# 7segement4digits1badidea-mk-4-smd.net
KiCad netlist of a schematic drawn in EAGLE
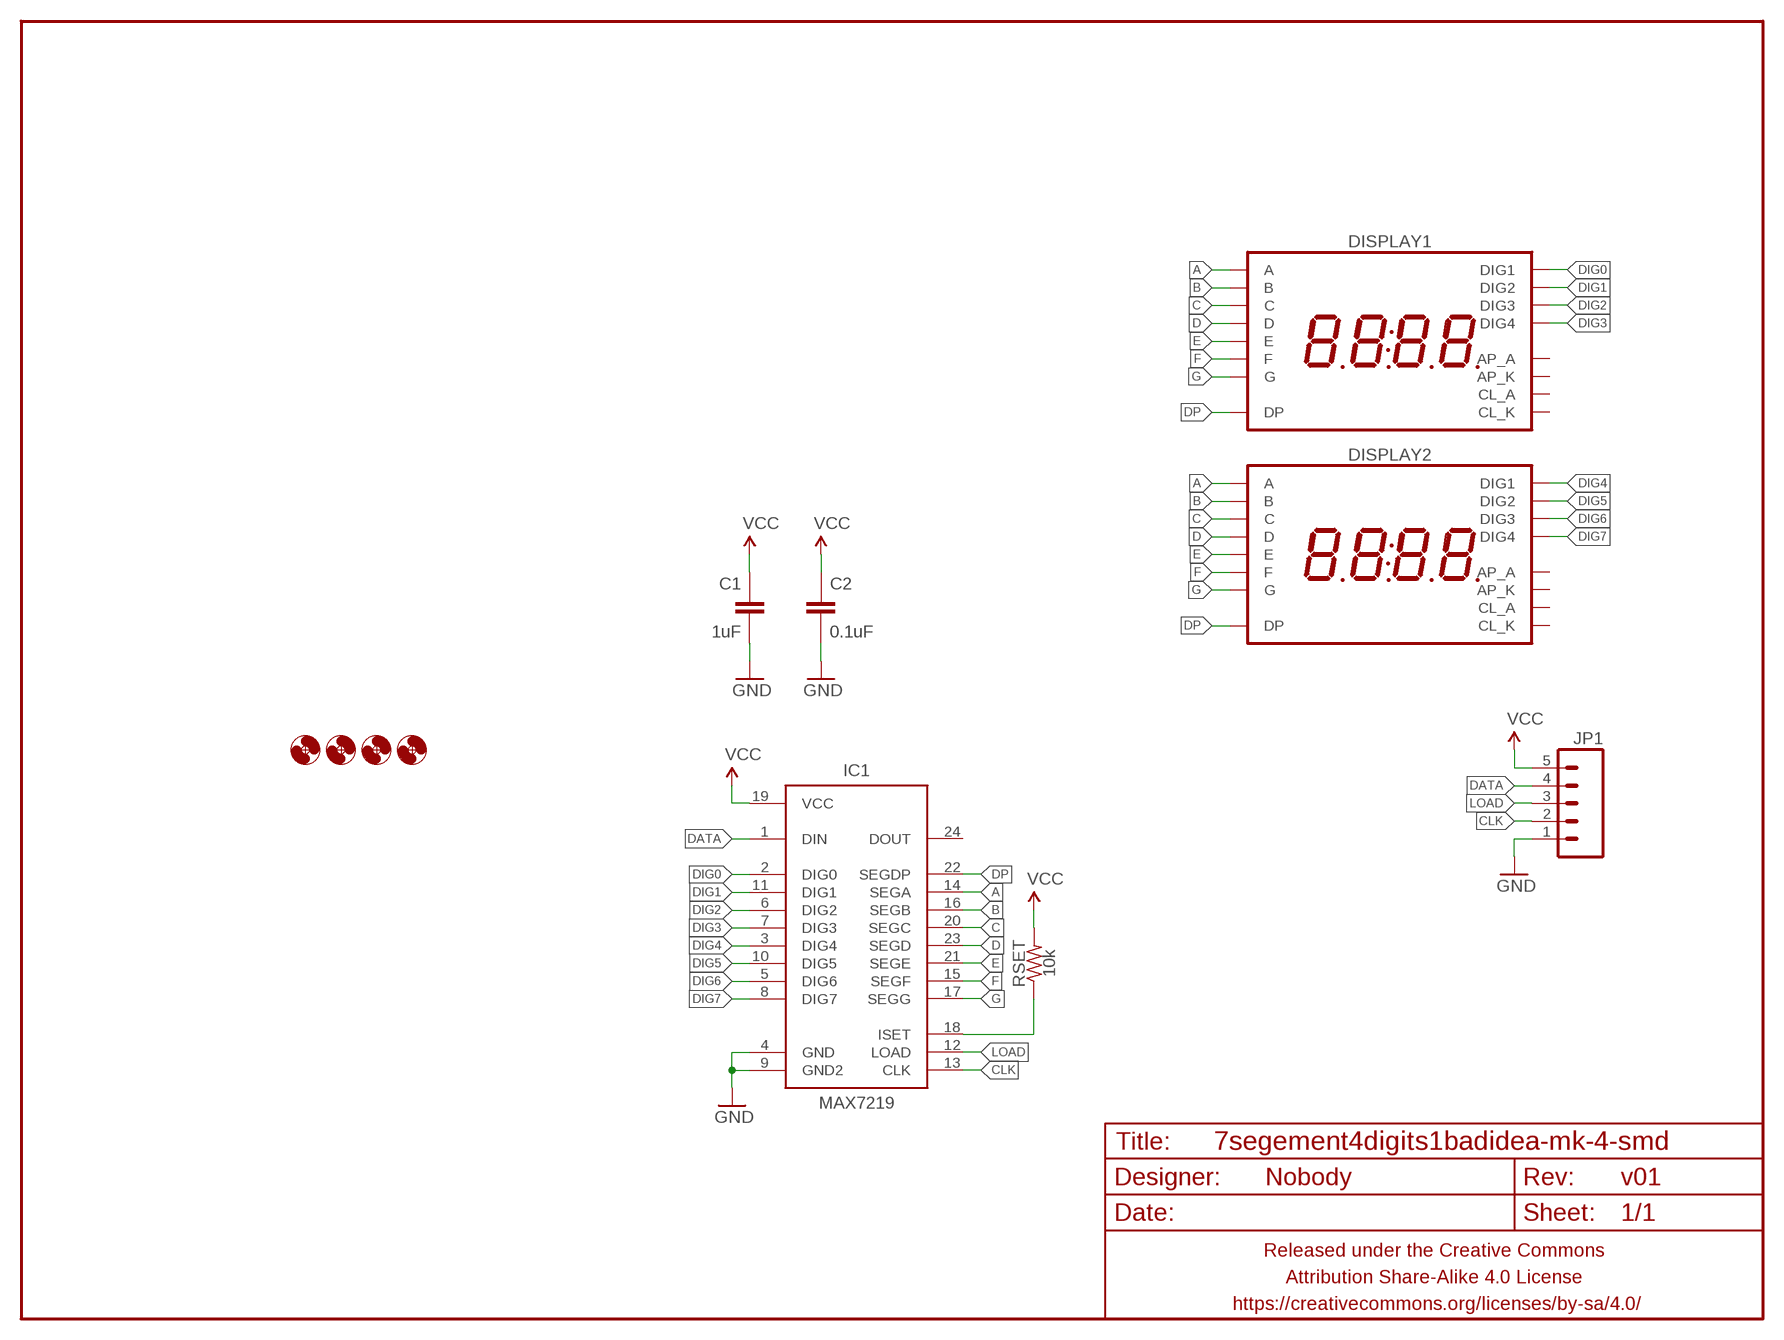
[diagram p0: schematic, sheet 1]

(export (version "E")
  (design (tool "Eeschema 10.0.6"))
  (components
    (comp (ref "C1")
      (value "1uF")
      (footprint "eagle-import:C025-024X044")
      (libsource (lib "eagle-import") (part "CAPACITOR-CERAMIC025-024X044"))
    )
    (comp (ref "C2")
      (value "0.1uF")
      (footprint "eagle-import:C025-024X044")
      (libsource (lib "eagle-import") (part "CAPACITOR-CERAMIC025-024X044"))
    )
    (comp (ref "DISPLAY1")
      (value "7SEG_4DIGIT_COLON_APOS")
      (footprint "eagle-import:7SEG_4DIG_10MM")
      (libsource (lib "eagle-import") (part "7SEG_4DIGIT_COLON_APOS"))
    )
    (comp (ref "DISPLAY2")
      (value "7SEG_4DIGIT_COLON_APOS")
      (footprint "eagle-import:7SEG_4DIG_10MM")
      (libsource (lib "eagle-import") (part "7SEG_4DIGIT_COLON_APOS"))
    )
    (comp (ref "FRAME1")
      (value "FRAME-LETTERNO_PACKAGE")
      (footprint "eagle-import:DUMMY")
      (fields (field (name "DESIGNER") "Nobody"))
      (libsource (lib "eagle-import") (part "FRAME-LETTERNO_PACKAGE"))
    )
    (comp (ref "H1")
      (value "HOLE#2")
      (footprint "eagle-import:HOLE-#2")
      (libsource (lib "eagle-import") (part "HOLE#2"))
    )
    (comp (ref "H2")
      (value "HOLE#2")
      (footprint "eagle-import:HOLE-#2")
      (libsource (lib "eagle-import") (part "HOLE#2"))
    )
    (comp (ref "H3")
      (value "HOLE#2")
      (footprint "eagle-import:HOLE-#2")
      (libsource (lib "eagle-import") (part "HOLE#2"))
    )
    (comp (ref "H4")
      (value "HOLE#2")
      (footprint "eagle-import:HOLE-#2")
      (libsource (lib "eagle-import") (part "HOLE#2"))
    )
    (comp (ref "IC1")
      (value "MAX7219")
      (footprint "eagle-import:SO24W")
      (libsource (lib "eagle-import") (part "MAX7219SOIC-W"))
    )
    (comp (ref "JP1")
      (value "M05PTH")
      (footprint "eagle-import:1X05")
      (libsource (lib "eagle-import") (part "M05PTH"))
    )
    (comp (ref "RSET")
      (value "10k")
      (footprint "eagle-import:RESISTOR-AXIAL-PTH-6.35MM")
      (libsource (lib "eagle-import") (part "RESISTORPTH-AXIAL-6.35MM"))
    )
  )
  (nets
    (net (code "1") (name "A") (class "Default")
      (node (ref "DISPLAY1") (pin "14") (pinfunction "A_14") (pintype "passive"))
      (node (ref "DISPLAY2") (pin "14") (pinfunction "A_14") (pintype "passive"))
      (node (ref "IC1") (pin "14") (pinfunction "SEGA_14") (pintype "bidirectional"))
    )
    (net (code "2") (name "B") (class "Default")
      (node (ref "DISPLAY1") (pin "16") (pinfunction "B_16") (pintype "passive"))
      (node (ref "DISPLAY2") (pin "16") (pinfunction "B_16") (pintype "passive"))
      (node (ref "IC1") (pin "16") (pinfunction "SEGB_16") (pintype "bidirectional"))
    )
    (net (code "3") (name "C") (class "Default")
      (node (ref "DISPLAY1") (pin "13") (pinfunction "C_13") (pintype "passive"))
      (node (ref "DISPLAY2") (pin "13") (pinfunction "C_13") (pintype "passive"))
      (node (ref "IC1") (pin "20") (pinfunction "SEGC_20") (pintype "bidirectional"))
    )
    (net (code "4") (name "CLK") (class "Default")
      (node (ref "IC1") (pin "13") (pinfunction "CLK_13") (pintype "bidirectional"))
      (node (ref "JP1") (pin "2") (pinfunction "2_2") (pintype "passive"))
    )
    (net (code "5") (name "D") (class "Default")
      (node (ref "DISPLAY1") (pin "3") (pinfunction "D_3") (pintype "passive"))
      (node (ref "DISPLAY2") (pin "3") (pinfunction "D_3") (pintype "passive"))
      (node (ref "IC1") (pin "23") (pinfunction "SEGD_23") (pintype "bidirectional"))
    )
    (net (code "6") (name "DATA") (class "Default")
      (node (ref "IC1") (pin "1") (pinfunction "DIN_1") (pintype "bidirectional"))
      (node (ref "JP1") (pin "4") (pinfunction "4_4") (pintype "passive"))
    )
    (net (code "7") (name "DIG0") (class "Default")
      (node (ref "DISPLAY1") (pin "1") (pinfunction "DIG1_1") (pintype "passive"))
      (node (ref "IC1") (pin "2") (pinfunction "DIG0_2") (pintype "bidirectional"))
    )
    (net (code "8") (name "DIG1") (class "Default")
      (node (ref "DISPLAY1") (pin "2") (pinfunction "DIG2_2") (pintype "passive"))
      (node (ref "IC1") (pin "11") (pinfunction "DIG1_11") (pintype "bidirectional"))
    )
    (net (code "9") (name "DIG2") (class "Default")
      (node (ref "DISPLAY1") (pin "6") (pinfunction "DIG3_6") (pintype "passive"))
      (node (ref "IC1") (pin "6") (pinfunction "DIG2_6") (pintype "bidirectional"))
    )
    (net (code "10") (name "DIG3") (class "Default")
      (node (ref "DISPLAY1") (pin "8") (pinfunction "DIG4_8") (pintype "passive"))
      (node (ref "IC1") (pin "7") (pinfunction "DIG3_7") (pintype "bidirectional"))
    )
    (net (code "11") (name "DIG4") (class "Default")
      (node (ref "DISPLAY2") (pin "1") (pinfunction "DIG1_1") (pintype "passive"))
      (node (ref "IC1") (pin "3") (pinfunction "DIG4_3") (pintype "bidirectional"))
    )
    (net (code "12") (name "DIG5") (class "Default")
      (node (ref "DISPLAY2") (pin "2") (pinfunction "DIG2_2") (pintype "passive"))
      (node (ref "IC1") (pin "10") (pinfunction "DIG5_10") (pintype "bidirectional"))
    )
    (net (code "13") (name "DIG6") (class "Default")
      (node (ref "DISPLAY2") (pin "6") (pinfunction "DIG3_6") (pintype "passive"))
      (node (ref "IC1") (pin "5") (pinfunction "DIG6_5") (pintype "bidirectional"))
    )
    (net (code "14") (name "DIG7") (class "Default")
      (node (ref "DISPLAY2") (pin "8") (pinfunction "DIG4_8") (pintype "passive"))
      (node (ref "IC1") (pin "8") (pinfunction "DIG7_8") (pintype "bidirectional"))
    )
    (net (code "15") (name "DP") (class "Default")
      (node (ref "DISPLAY1") (pin "7") (pinfunction "DP_7") (pintype "passive"))
      (node (ref "DISPLAY2") (pin "7") (pinfunction "DP_7") (pintype "passive"))
      (node (ref "IC1") (pin "22") (pinfunction "SEGDP_22") (pintype "bidirectional"))
    )
    (net (code "16") (name "E") (class "Default")
      (node (ref "DISPLAY1") (pin "5") (pinfunction "E_5") (pintype "passive"))
      (node (ref "DISPLAY2") (pin "5") (pinfunction "E_5") (pintype "passive"))
      (node (ref "IC1") (pin "21") (pinfunction "SEGE_21") (pintype "bidirectional"))
    )
    (net (code "17") (name "F") (class "Default")
      (node (ref "DISPLAY1") (pin "11") (pinfunction "F_11") (pintype "passive"))
      (node (ref "DISPLAY2") (pin "11") (pinfunction "F_11") (pintype "passive"))
      (node (ref "IC1") (pin "15") (pinfunction "SEGF_15") (pintype "bidirectional"))
    )
    (net (code "18") (name "G") (class "Default")
      (node (ref "DISPLAY1") (pin "15") (pinfunction "G_15") (pintype "passive"))
      (node (ref "DISPLAY2") (pin "15") (pinfunction "G_15") (pintype "passive"))
      (node (ref "IC1") (pin "17") (pinfunction "SEGG_17") (pintype "bidirectional"))
    )
    (net (code "19") (name "GND") (class "Default")
      (node (ref "C1") (pin "2") (pinfunction "2_2") (pintype "passive"))
      (node (ref "C2") (pin "2") (pinfunction "2_2") (pintype "passive"))
      (node (ref "IC1") (pin "4") (pinfunction "GND_4") (pintype "bidirectional"))
      (node (ref "IC1") (pin "9") (pinfunction "GND2_9") (pintype "bidirectional"))
      (node (ref "JP1") (pin "1") (pinfunction "1_1") (pintype "passive"))
    )
    (net (code "20") (name "LOAD") (class "Default")
      (node (ref "IC1") (pin "12") (pinfunction "LOAD_12") (pintype "bidirectional"))
      (node (ref "JP1") (pin "3") (pinfunction "3_3") (pintype "passive"))
    )
    (net (code "21") (name "Net-(IC1-ISET)") (class "Default")
      (node (ref "IC1") (pin "18") (pinfunction "ISET_18") (pintype "bidirectional"))
      (node (ref "RSET") (pin "P$1") (pinfunction "1_P$1") (pintype "passive"))
    )
    (net (code "22") (name "VCC") (class "Default")
      (node (ref "C1") (pin "1") (pinfunction "1_1") (pintype "passive"))
      (node (ref "C2") (pin "1") (pinfunction "1_1") (pintype "passive"))
      (node (ref "IC1") (pin "19") (pinfunction "VCC_19") (pintype "bidirectional"))
      (node (ref "JP1") (pin "5") (pinfunction "5_5") (pintype "passive"))
      (node (ref "RSET") (pin "P$2") (pinfunction "2_P$2") (pintype "passive"))
    )
    (net (code "23") (name "unconnected-(DISPLAY1-AP_A-Pad10)") (class "Default")
      (node (ref "DISPLAY1") (pin "10") (pinfunction "AP_A_10") (pintype "bidirectional"))
    )
    (net (code "24") (name "unconnected-(DISPLAY1-AP_K-Pad9)") (class "Default")
      (node (ref "DISPLAY1") (pin "9") (pinfunction "AP_K_9") (pintype "bidirectional"))
    )
    (net (code "25") (name "unconnected-(DISPLAY1-CL_A-Pad4)") (class "Default")
      (node (ref "DISPLAY1") (pin "4") (pinfunction "CL_A_4") (pintype "passive"))
    )
    (net (code "26") (name "unconnected-(DISPLAY1-CL_K-Pad12)") (class "Default")
      (node (ref "DISPLAY1") (pin "12") (pinfunction "CL_K_12") (pintype "passive"))
    )
    (net (code "27") (name "unconnected-(DISPLAY2-AP_A-Pad10)") (class "Default")
      (node (ref "DISPLAY2") (pin "10") (pinfunction "AP_A_10") (pintype "bidirectional"))
    )
    (net (code "28") (name "unconnected-(DISPLAY2-AP_K-Pad9)") (class "Default")
      (node (ref "DISPLAY2") (pin "9") (pinfunction "AP_K_9") (pintype "bidirectional"))
    )
    (net (code "29") (name "unconnected-(DISPLAY2-CL_A-Pad4)") (class "Default")
      (node (ref "DISPLAY2") (pin "4") (pinfunction "CL_A_4") (pintype "passive"))
    )
    (net (code "30") (name "unconnected-(DISPLAY2-CL_K-Pad12)") (class "Default")
      (node (ref "DISPLAY2") (pin "12") (pinfunction "CL_K_12") (pintype "passive"))
    )
    (net (code "31") (name "unconnected-(IC1-DOUT-Pad24)") (class "Default")
      (node (ref "IC1") (pin "24") (pinfunction "DOUT_24") (pintype "bidirectional"))
    )
  )
)
